# magnetophone.net
KiCad netlist of a schematic drawn in EAGLE
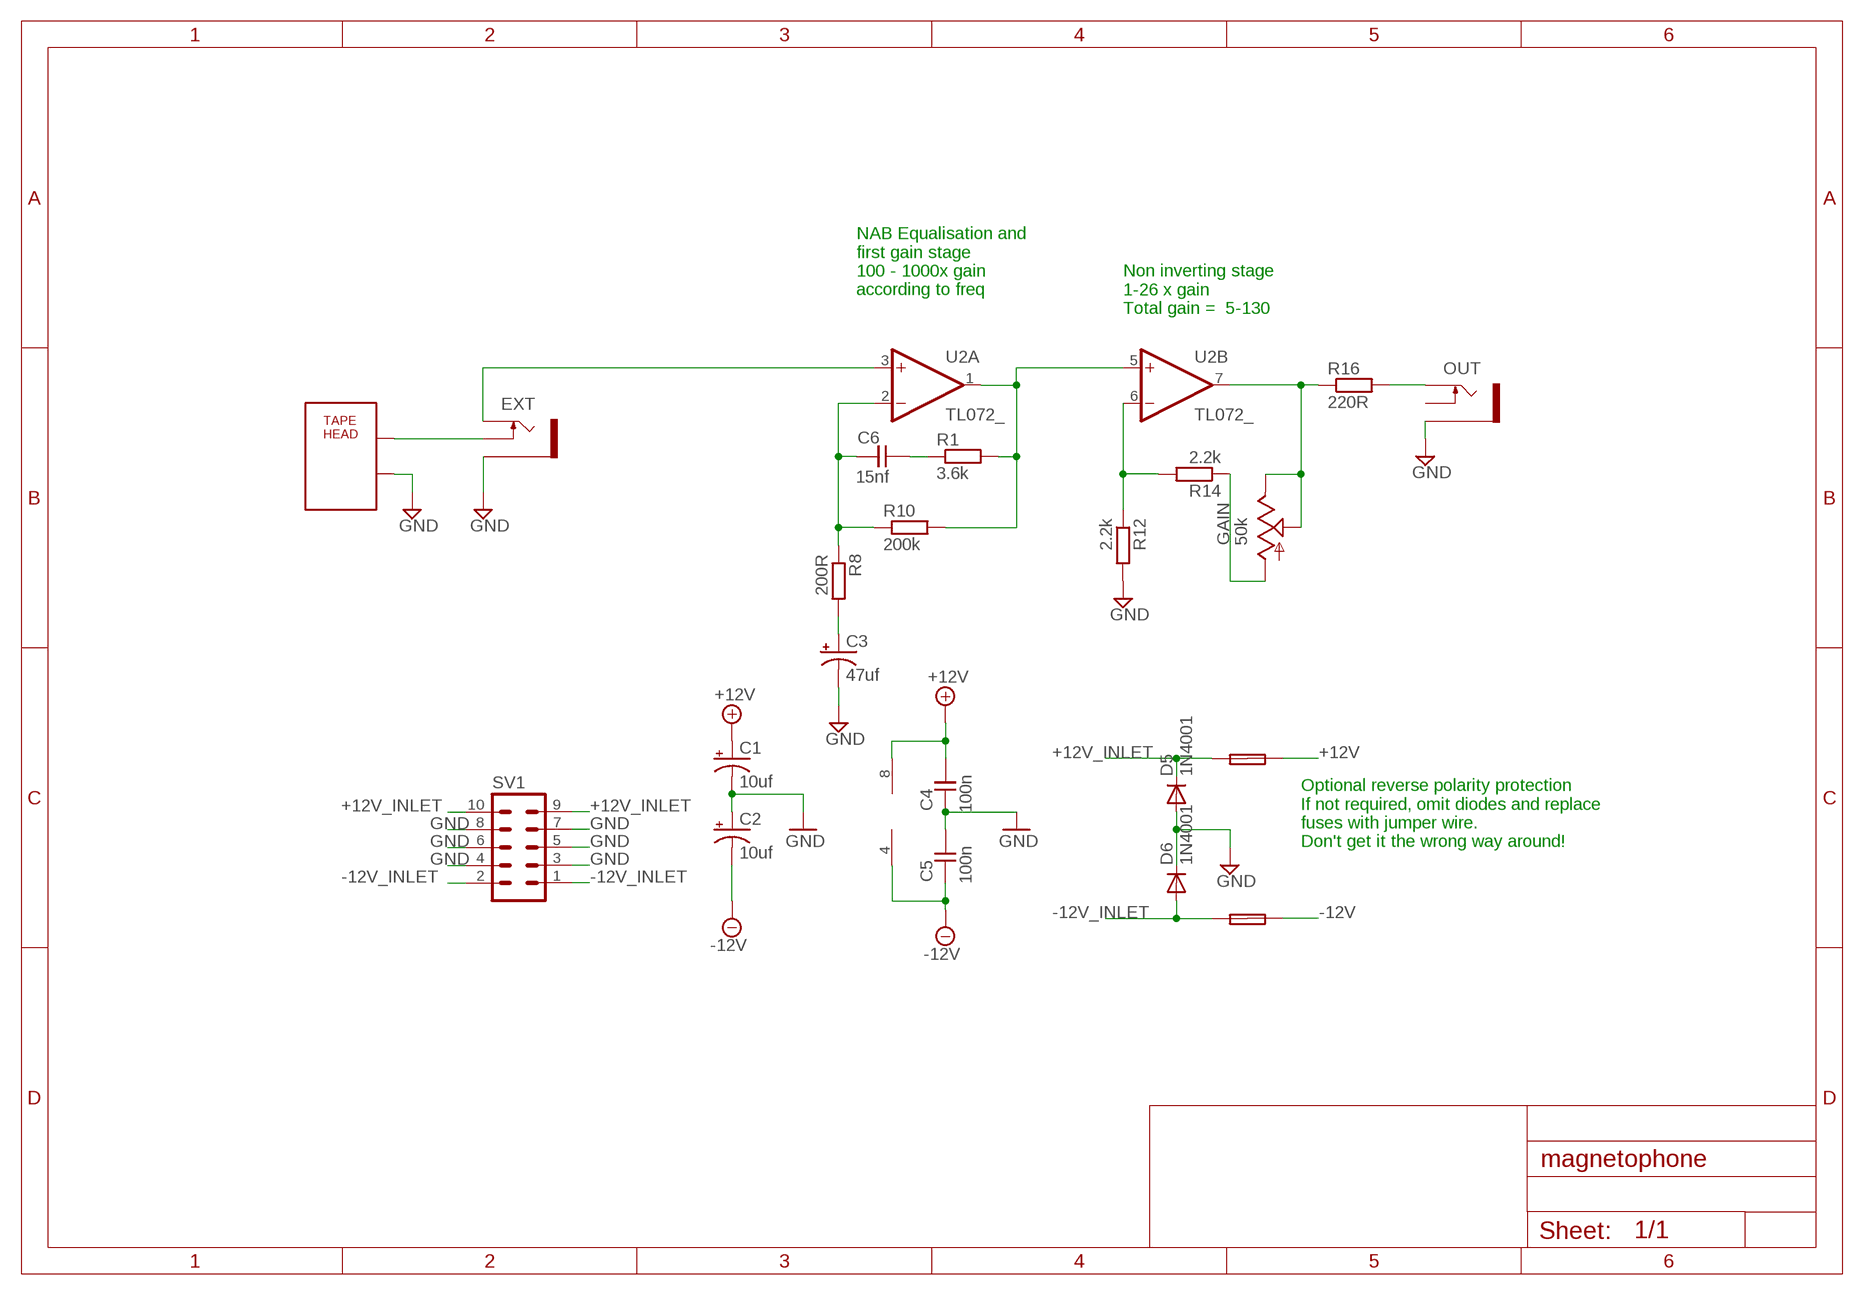
[diagram p0: schematic, sheet 1]

(export (version "E")
  (design (tool "Eeschema 10.0.6"))
  (components
    (comp (ref "1")
      (value "FUSE")
      (footprint "eagle-import:C050H075X075")
      (libsource (lib "eagle-import") (part "PTC_FUSEPOLY_FUSE"))
    )
    (comp (ref "C1")
      (value "10uf")
      (footprint "eagle-import:CPOL-RADIAL-10UF-25V")
      (libsource (lib "eagle-import") (part "CAP_POLPTH2"))
    )
    (comp (ref "C2")
      (value "10uf")
      (footprint "eagle-import:CPOL-RADIAL-10UF-25V")
      (libsource (lib "eagle-import") (part "CAP_POLPTH2"))
    )
    (comp (ref "C3")
      (value "47uf")
      (footprint "eagle-import:CPOL-RADIAL-10UF-25V")
      (libsource (lib "eagle-import") (part "CAP_POLPTH2"))
    )
    (comp (ref "C4")
      (value "100n")
      (footprint "eagle-import:C050-024X044")
      (libsource (lib "eagle-import") (part "C-EU050-024X044"))
    )
    (comp (ref "C5")
      (value "100n")
      (footprint "eagle-import:C050-024X044")
      (libsource (lib "eagle-import") (part "C-EU050-024X044"))
    )
    (comp (ref "C6")
      (value "15nf")
      (footprint "eagle-import:C050-024X044")
      (libsource (lib "eagle-import") (part "C-EU050-024X044"))
    )
    (comp (ref "D5")
      (value "1N4001")
      (footprint "eagle-import:DO41-10")
      (libsource (lib "eagle-import") (part "1N4004"))
    )
    (comp (ref "D6")
      (value "1N4001")
      (footprint "eagle-import:DO41-10")
      (libsource (lib "eagle-import") (part "1N4004"))
    )
    (comp (ref "EXT")
      (value "THONKICONNNEW")
      (footprint "eagle-import:WQP-PJ301M-12_JACK")
      (libsource (lib "eagle-import") (part "THONKICONNNEW"))
    )
    (comp (ref "FUSE")
      (value "FUSE")
      (footprint "eagle-import:C050H075X075")
      (libsource (lib "eagle-import") (part "PTC_FUSEPOLY_FUSE"))
    )
    (comp (ref "GAIN")
      (value "50k")
      (footprint "eagle-import:EVUF")
      (libsource (lib "eagle-import") (part "ALPHA-9MMAF2"))
    )
    (comp (ref "OUT")
      (value "THONKICONNNEW")
      (footprint "eagle-import:WQP-PJ301M-12_JACK")
      (libsource (lib "eagle-import") (part "THONKICONNNEW"))
    )
    (comp (ref "R1")
      (value "3.6k")
      (footprint "eagle-import:7MM_RESISTOR")
      (libsource (lib "eagle-import") (part "RESISTOR7MM"))
    )
    (comp (ref "R8")
      (value "200R")
      (footprint "eagle-import:7MM_RESISTOR")
      (libsource (lib "eagle-import") (part "RESISTOR7MM"))
    )
    (comp (ref "R10")
      (value "200k")
      (footprint "eagle-import:7MM_RESISTOR")
      (libsource (lib "eagle-import") (part "RESISTOR7MM"))
    )
    (comp (ref "R12")
      (value "2.2k")
      (footprint "eagle-import:7MM_RESISTOR")
      (libsource (lib "eagle-import") (part "RESISTOR7MM"))
    )
    (comp (ref "R14")
      (value "2.2k")
      (footprint "eagle-import:7MM_RESISTOR")
      (libsource (lib "eagle-import") (part "RESISTOR7MM"))
    )
    (comp (ref "R16")
      (value "220R")
      (footprint "eagle-import:7MM_RESISTOR")
      (libsource (lib "eagle-import") (part "RESISTOR7MM"))
    )
    (comp (ref "SV1")
      (value "10_PIN_HEADER")
      (footprint "eagle-import:MA05-2")
      (libsource (lib "eagle-import") (part "10_PIN_HEADER"))
    )
    (comp (ref "U$1")
      (value "MONO_CASSETTE_HEAD")
      (footprint "eagle-import:MONO_CASSETTE_HEAD")
      (libsource (lib "eagle-import") (part "MONO_CASSETTE_HEAD"))
    )
    (comp (ref "U2")
      (value "TL072_")
      (footprint "eagle-import:DIL08")
      (libsource (lib "eagle-import") (part "TL072_"))
    )
  )
  (nets
    (net (code "1") (name "+12V") (class "Default")
      (node (ref "1") (pin "2") (pinfunction "P$2_2") (pintype "bidirectional"))
      (node (ref "C1") (pin "1") (pinfunction "+_1") (pintype "passive"))
      (node (ref "C4") (pin "1") (pinfunction "1_1") (pintype "passive"))
      (node (ref "U2") (pin "8") (pinfunction "V+_8") (pintype "power_in"))
    )
    (net (code "2") (name "-12V") (class "Default")
      (node (ref "C2") (pin "2") (pinfunction "-_2") (pintype "passive"))
      (node (ref "C5") (pin "2") (pinfunction "2_2") (pintype "passive"))
      (node (ref "FUSE") (pin "2") (pinfunction "P$2_2") (pintype "bidirectional"))
      (node (ref "U2") (pin "4") (pinfunction "V-_4") (pintype "power_in"))
    )
    (net (code "3") (name "/+12V_INLET") (class "Default")
      (node (ref "1") (pin "1") (pinfunction "P$1_1") (pintype "bidirectional"))
      (node (ref "D5") (pin "C") (pinfunction "C_C") (pintype "passive"))
      (node (ref "SV1") (pin "10") (pinfunction "10_10") (pintype "passive"))
      (node (ref "SV1") (pin "9") (pinfunction "9_9") (pintype "passive"))
    )
    (net (code "4") (name "/-12V_INLET") (class "Default")
      (node (ref "D6") (pin "A") (pinfunction "A_A") (pintype "passive"))
      (node (ref "FUSE") (pin "1") (pinfunction "P$1_1") (pintype "bidirectional"))
      (node (ref "SV1") (pin "1") (pinfunction "1_1") (pintype "passive"))
      (node (ref "SV1") (pin "2") (pinfunction "2_2") (pintype "passive"))
    )
    (net (code "5") (name "GND") (class "Default")
      (node (ref "C1") (pin "2") (pinfunction "-_2") (pintype "passive"))
      (node (ref "C2") (pin "1") (pinfunction "+_1") (pintype "passive"))
      (node (ref "C3") (pin "2") (pinfunction "-_2") (pintype "passive"))
      (node (ref "C4") (pin "2") (pinfunction "2_2") (pintype "passive"))
      (node (ref "C5") (pin "1") (pinfunction "1_1") (pintype "passive"))
      (node (ref "D5") (pin "A") (pinfunction "A_A") (pintype "passive"))
      (node (ref "D6") (pin "C") (pinfunction "C_C") (pintype "passive"))
      (node (ref "EXT") (pin "P$3_SLEEVE") (pinfunction "SLEEVE_P$3_SLEEVE") (pintype "passive"))
      (node (ref "OUT") (pin "P$3_SLEEVE") (pinfunction "SLEEVE_P$3_SLEEVE") (pintype "passive"))
      (node (ref "R12") (pin "2") (pinfunction "2_2") (pintype "passive"))
      (node (ref "SV1") (pin "3") (pinfunction "3_3") (pintype "passive"))
      (node (ref "SV1") (pin "4") (pinfunction "4_4") (pintype "passive"))
      (node (ref "SV1") (pin "5") (pinfunction "5_5") (pintype "passive"))
      (node (ref "SV1") (pin "6") (pinfunction "6_6") (pintype "passive"))
      (node (ref "SV1") (pin "7") (pinfunction "7_7") (pintype "passive"))
      (node (ref "SV1") (pin "8") (pinfunction "8_8") (pintype "passive"))
      (node (ref "U$1") (pin "P$2") (pinfunction "P$2_P$2") (pintype "bidirectional"))
    )
    (net (code "6") (name "Net-(C3-+)") (class "Default")
      (node (ref "C3") (pin "1") (pinfunction "+_1") (pintype "passive"))
      (node (ref "R8") (pin "2") (pinfunction "2_2") (pintype "passive"))
    )
    (net (code "7") (name "Net-(C6-Pad1)") (class "Default")
      (node (ref "C6") (pin "1") (pinfunction "1_1") (pintype "passive"))
      (node (ref "R1") (pin "1") (pinfunction "1_1") (pintype "passive"))
    )
    (net (code "8") (name "Net-(EXT-SWITCH)") (class "Default")
      (node (ref "EXT") (pin "P$2_SWITCH") (pinfunction "SWITCH_P$2_SWITCH") (pintype "passive"))
      (node (ref "U$1") (pin "P$1") (pinfunction "P$1_P$1") (pintype "bidirectional"))
    )
    (net (code "9") (name "Net-(EXT-TIP)") (class "Default")
      (node (ref "EXT") (pin "P$1_TIP") (pinfunction "TIP_P$1_TIP") (pintype "passive"))
      (node (ref "U2") (pin "3") (pinfunction "+IN_3") (pintype "input"))
    )
    (net (code "10") (name "Net-(GAIN-A)") (class "Default")
      (node (ref "GAIN") (pin "1") (pinfunction "A_1") (pintype "passive"))
      (node (ref "R14") (pin "1") (pinfunction "1_1") (pintype "passive"))
    )
    (net (code "11") (name "Net-(GAIN-E)") (class "Default")
      (node (ref "GAIN") (pin "2") (pinfunction "S_2") (pintype "passive"))
      (node (ref "GAIN") (pin "3") (pinfunction "E_3") (pintype "passive"))
      (node (ref "R16") (pin "1") (pinfunction "1_1") (pintype "passive"))
      (node (ref "U2") (pin "7") (pinfunction "OUT_7") (pintype "output"))
    )
    (net (code "12") (name "Net-(OUT-TIP)") (class "Default")
      (node (ref "OUT") (pin "P$1_TIP") (pinfunction "TIP_P$1_TIP") (pintype "passive"))
      (node (ref "R16") (pin "2") (pinfunction "2_2") (pintype "passive"))
    )
    (net (code "13") (name "Net-(U2A--IN)") (class "Default")
      (node (ref "C6") (pin "2") (pinfunction "2_2") (pintype "passive"))
      (node (ref "R10") (pin "1") (pinfunction "1_1") (pintype "passive"))
      (node (ref "R8") (pin "1") (pinfunction "1_1") (pintype "passive"))
      (node (ref "U2") (pin "2") (pinfunction "-IN_2") (pintype "input"))
    )
    (net (code "14") (name "Net-(U2A-OUT)") (class "Default")
      (node (ref "R1") (pin "2") (pinfunction "2_2") (pintype "passive"))
      (node (ref "R10") (pin "2") (pinfunction "2_2") (pintype "passive"))
      (node (ref "U2") (pin "1") (pinfunction "OUT_1") (pintype "output"))
      (node (ref "U2") (pin "5") (pinfunction "+IN_5") (pintype "input"))
    )
    (net (code "15") (name "Net-(U2B--IN)") (class "Default")
      (node (ref "R12") (pin "1") (pinfunction "1_1") (pintype "passive"))
      (node (ref "R14") (pin "2") (pinfunction "2_2") (pintype "passive"))
      (node (ref "U2") (pin "6") (pinfunction "-IN_6") (pintype "input"))
    )
    (net (code "16") (name "unconnected-(OUT-SWITCH-PadP$2_SWITCH)") (class "Default")
      (node (ref "OUT") (pin "P$2_SWITCH") (pinfunction "SWITCH_P$2_SWITCH") (pintype "passive"))
    )
  )
)
